# BAI1.net
KiCad netlist of a schematic drawn in Altium Designer
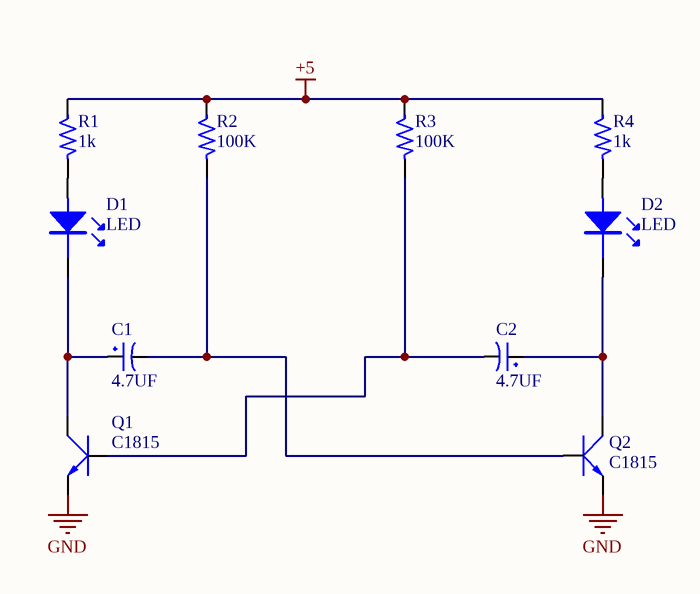
[diagram p0: BAI1.SchDoc]

(export (version "E")
  (design (tool "Eeschema 10.0.6"))
  (components
    (comp (ref "C1")
      (value "4.7UF")
      (footprint "CP1/2")
      (description "Cap P  0,1uF < 22uF , 16 - 50V")
      (libsource (lib "Cty1") (part "CP1"))
    )
    (comp (ref "C2")
      (value "4.7UF")
      (footprint "CP1/2")
      (description "Cap P  0,1uF < 22uF , 16 - 50V")
      (libsource (lib "Cty1") (part "CP1"))
    )
    (comp (ref "D1") (value "LED") (footprint "CAP10UF") (libsource (lib "Cty1") (part "LED")))
    (comp (ref "D2") (value "LED") (footprint "CAP10UF") (libsource (lib "Cty1") (part "LED")))
    (comp (ref "Q1")
      (value "C1815")
      (footprint "TO126")
      (description "NPN 600mW, ECB")
      (libsource (lib "Cty1") (part "C1815"))
    )
    (comp (ref "Q2")
      (value "C1815")
      (footprint "TO126")
      (description "NPN 600mW, ECB")
      (libsource (lib "Cty1") (part "C1815"))
    )
    (comp (ref "R1")
      (value "1k")
      (footprint "R1/6W")
      (description "Resistor 1/4W")
      (libsource (lib "Cty1") (part "Res"))
    )
    (comp (ref "R2")
      (value "100K")
      (footprint "R1/6W")
      (description "Resistor 1/4W")
      (libsource (lib "Cty1") (part "Res"))
    )
    (comp (ref "R3")
      (value "100K")
      (footprint "R1/6W")
      (description "Resistor 1/4W")
      (libsource (lib "Cty1") (part "Res"))
    )
    (comp (ref "R4")
      (value "1k")
      (footprint "R1/6W")
      (description "Resistor 1/4W")
      (libsource (lib "Cty1") (part "Res"))
    )
  )
  (nets
    (net (code "1") (name "+5") (class "Default")
      (node (ref "R1") (pin "1") (pinfunction "1_1") (pintype "passive"))
      (node (ref "R2") (pin "1") (pinfunction "1_1") (pintype "passive"))
      (node (ref "R3") (pin "1") (pinfunction "1_1") (pintype "passive"))
      (node (ref "R4") (pin "1") (pinfunction "1_1") (pintype "passive"))
    )
    (net (code "2") (name "GND") (class "Default")
      (node (ref "Q1") (pin "3") (pinfunction "E_3") (pintype "passive"))
      (node (ref "Q2") (pin "3") (pinfunction "E_3") (pintype "passive"))
    )
    (net (code "3") (name "Net-(D1-Pad1)") (class "Default")
      (node (ref "D1") (pin "1") (pinfunction "1_1") (pintype "passive"))
      (node (ref "R1") (pin "2") (pinfunction "2_2") (pintype "passive"))
    )
    (net (code "4") (name "Net-(D2-Pad1)") (class "Default")
      (node (ref "D2") (pin "1") (pinfunction "1_1") (pintype "passive"))
      (node (ref "R4") (pin "2") (pinfunction "2_2") (pintype "passive"))
    )
    (net (code "5") (name "Net-(Q1-B)") (class "Default")
      (node (ref "C2") (pin "2") (pinfunction "2_2") (pintype "passive"))
      (node (ref "Q1") (pin "1") (pinfunction "B_1") (pintype "passive"))
      (node (ref "R3") (pin "2") (pinfunction "2_2") (pintype "passive"))
    )
    (net (code "6") (name "Net-(Q1-C)") (class "Default")
      (node (ref "C1") (pin "1") (pinfunction "1_1") (pintype "passive"))
      (node (ref "D1") (pin "2") (pinfunction "2_2") (pintype "passive"))
      (node (ref "Q1") (pin "2") (pinfunction "C_2") (pintype "passive"))
    )
    (net (code "7") (name "Net-(Q2-B)") (class "Default")
      (node (ref "C1") (pin "2") (pinfunction "2_2") (pintype "passive"))
      (node (ref "Q2") (pin "1") (pinfunction "B_1") (pintype "passive"))
      (node (ref "R2") (pin "2") (pinfunction "2_2") (pintype "passive"))
    )
    (net (code "8") (name "Net-(Q2-C)") (class "Default")
      (node (ref "C2") (pin "1") (pinfunction "1_1") (pintype "passive"))
      (node (ref "D2") (pin "2") (pinfunction "2_2") (pintype "passive"))
      (node (ref "Q2") (pin "2") (pinfunction "C_2") (pintype "passive"))
    )
  )
)
